# BLE_Mate2.net
KiCad netlist of a schematic drawn in EAGLE
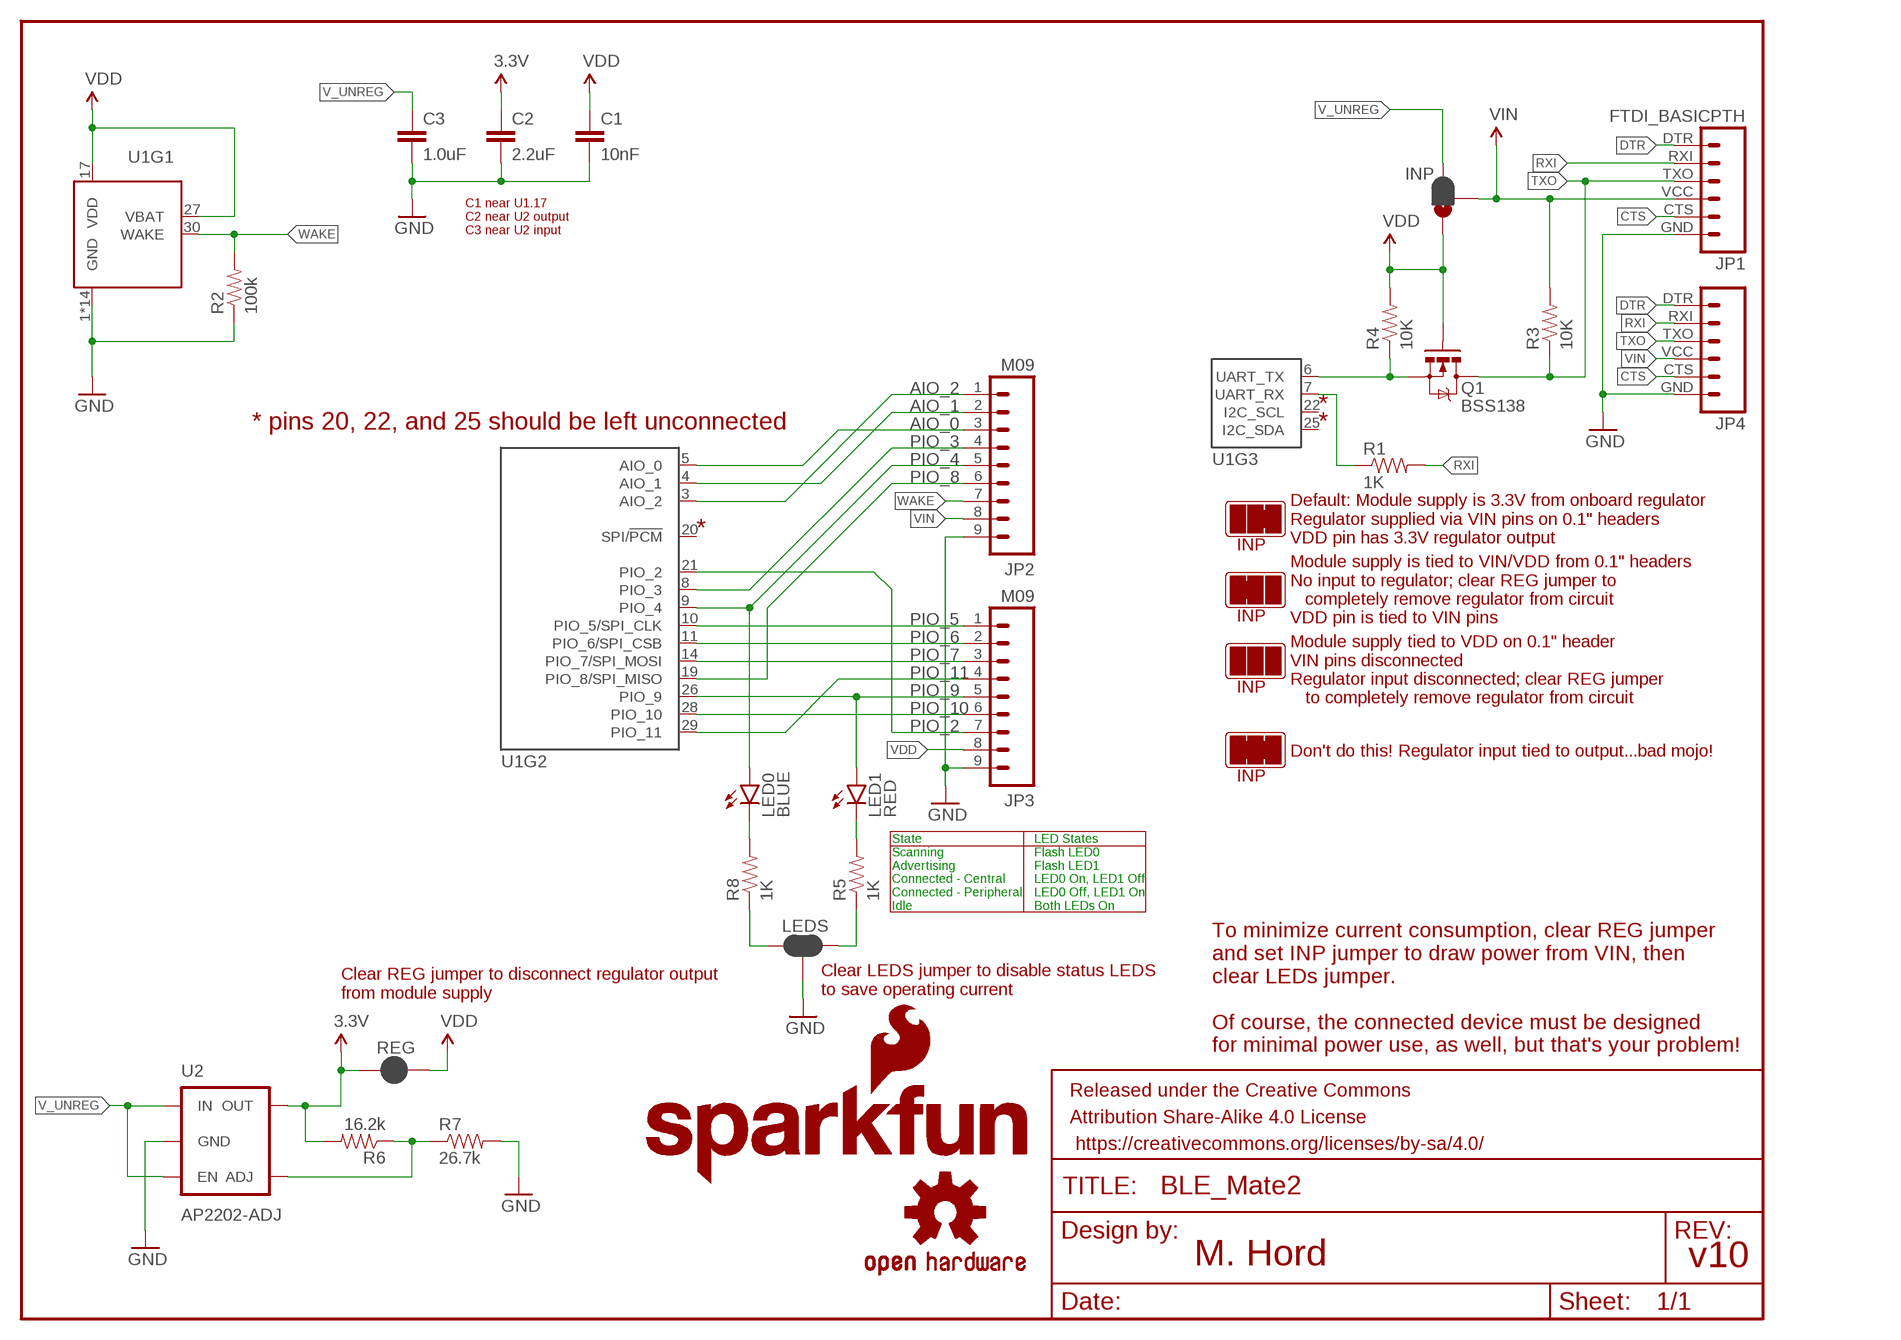
[diagram p0: schematic, sheet 1]

(export (version "E")
  (design (tool "Eeschema 10.0.6"))
  (components
    (comp (ref "C1")
      (value "10nF")
      (footprint "eagle-import:0603-CAP")
      (libsource (lib "eagle-import") (part "10NF/10000PF-50V-10%(0603)"))
    )
    (comp (ref "C2")
      (value "2.2uF")
      (footprint "eagle-import:0603-CAP")
      (libsource (lib "eagle-import") (part "2.2UF-10V-20%(0603)"))
    )
    (comp (ref "C3")
      (value "1.0uF")
      (footprint "eagle-import:0603-CAP")
      (libsource (lib "eagle-import") (part "1.0UF-16V-10%(0603)"))
    )
    (comp (ref "FRAME1")
      (value "FRAME-LETTER")
      (footprint "eagle-import:CREATIVE_COMMONS")
      (libsource (lib "eagle-import") (part "FRAME-LETTER"))
    )
    (comp (ref "INP")
      (value "JUMPER-PAD-3-2OF3_NC_BY_PASTE")
      (footprint "eagle-import:PAD-JUMPER-3-2OF3_NC_BY_PASTE_YES_SILK_FULL_BOX")
      (libsource (lib "eagle-import") (part "JUMPER-PAD-3-2OF3_NC_BY_PASTE"))
    )
    (comp (ref "JP1")
      (value "FTDI_BASICPTH")
      (footprint "eagle-import:FTDI_BASIC")
      (libsource (lib "eagle-import") (part "FTDI_BASICPTH"))
    )
    (comp (ref "JP2")
      (value "M09")
      (footprint "eagle-import:1X09")
      (libsource (lib "eagle-import") (part "M09"))
    )
    (comp (ref "JP3")
      (value "M09")
      (footprint "eagle-import:1X09")
      (libsource (lib "eagle-import") (part "M09"))
    )
    (comp (ref "JP4")
      (value "M06SIP")
      (footprint "eagle-import:1X06")
      (libsource (lib "eagle-import") (part "M06SIP"))
    )
    (comp (ref "LED0")
      (value "BLUE")
      (footprint "eagle-import:LED-0603")
      (libsource (lib "eagle-import") (part "LED-BLUE0603"))
    )
    (comp (ref "LED1")
      (value "RED")
      (footprint "eagle-import:LED-0603")
      (libsource (lib "eagle-import") (part "LED-RED0603"))
    )
    (comp (ref "LEDS")
      (value "JUMPER-PAD-3-NC_BY_PASTE")
      (footprint "eagle-import:PAD-JUMPER-3-NC_BY_PASTE_YES_SILK_FULL_BOX")
      (libsource (lib "eagle-import") (part "JUMPER-PAD-3-NC_BY_PASTE"))
    )
    (comp (ref "LOGO1")
      (value "SFE_LOGO_NAME.1_INCH")
      (footprint "eagle-import:SFE_LOGO_NAME_.1")
      (libsource (lib "eagle-import") (part "SFE_LOGO_NAME.1_INCH"))
    )
    (comp (ref "LOGO2")
      (value "OSHW-LOGOS")
      (footprint "eagle-import:OSHW-LOGO-S")
      (libsource (lib "eagle-import") (part "OSHW-LOGOS"))
    )
    (comp (ref "LOGO3")
      (value "SFE_LOGO_NAME_FLAME.1_INCH")
      (footprint "eagle-import:SFE_LOGO_NAME_FLAME_.1")
      (libsource (lib "eagle-import") (part "SFE_LOGO_NAME_FLAME.1_INCH"))
    )
    (comp (ref "LOGO4")
      (value "OSHW-LOGOS")
      (footprint "eagle-import:OSHW-LOGO-S")
      (libsource (lib "eagle-import") (part "OSHW-LOGOS"))
    )
    (comp (ref "Q1")
      (value "BSS138")
      (footprint "eagle-import:SOT23")
      (libsource (lib "eagle-import") (part "MOSFET-NCHANNELBSS138"))
    )
    (comp (ref "R1")
      (value "1K")
      (footprint "eagle-import:0603-RES")
      (libsource (lib "eagle-import") (part "1KOHM1/10W1%(0603)"))
    )
    (comp (ref "R2")
      (value "100k")
      (footprint "eagle-import:0603-RES")
      (libsource (lib "eagle-import") (part "100KOHM1/10W1%(0603)"))
    )
    (comp (ref "R3")
      (value "10K")
      (footprint "eagle-import:0603-RES")
      (libsource (lib "eagle-import") (part "10KOHM1/10W1%(0603)0603"))
    )
    (comp (ref "R4")
      (value "10K")
      (footprint "eagle-import:0603-RES")
      (libsource (lib "eagle-import") (part "10KOHM1/10W1%(0603)0603"))
    )
    (comp (ref "R5")
      (value "1K")
      (footprint "eagle-import:0603-RES")
      (libsource (lib "eagle-import") (part "1KOHM1/10W1%(0603)"))
    )
    (comp (ref "R6")
      (value "16.2k")
      (footprint "eagle-import:0603-RES")
      (libsource (lib "eagle-import") (part "16.2KOHM1/10W1%(0603)"))
    )
    (comp (ref "R7")
      (value "26.7k")
      (footprint "eagle-import:0603-RES")
      (libsource (lib "eagle-import") (part "16.2KOHM1/10W1%(0603)"))
    )
    (comp (ref "R8")
      (value "1K")
      (footprint "eagle-import:0603-RES")
      (libsource (lib "eagle-import") (part "1KOHM1/10W1%(0603)"))
    )
    (comp (ref "REG")
      (value "JUMPER-PAD-2-NC_BY_PASTE")
      (footprint "eagle-import:PAD-JUMPER-2-NC_BY_PASTE_YES_SILK")
      (libsource (lib "eagle-import") (part "JUMPER-PAD-2-NC_BY_PASTE"))
    )
    (comp (ref "U1")
      (value "BC118")
      (footprint "eagle-import:BC118")
      (libsource (lib "eagle-import") (part "BC118"))
    )
    (comp (ref "U2")
      (value "AP2202-ADJ")
      (footprint "eagle-import:SOT23-5")
      (libsource (lib "eagle-import") (part "AP2202-ADJ"))
    )
  )
  (nets
    (net (code "1") (name "/AIO_0") (class "Default")
      (node (ref "JP2") (pin "3") (pinfunction "3_3") (pintype "passive"))
      (node (ref "U1") (pin "5") (pinfunction "AIO_0_5") (pintype "bidirectional"))
    )
    (net (code "2") (name "/AIO_1") (class "Default")
      (node (ref "JP2") (pin "2") (pinfunction "2_2") (pintype "passive"))
      (node (ref "U1") (pin "4") (pinfunction "AIO_1_4") (pintype "bidirectional"))
    )
    (net (code "3") (name "/AIO_2") (class "Default")
      (node (ref "JP2") (pin "1") (pinfunction "1_1") (pintype "passive"))
      (node (ref "U1") (pin "3") (pinfunction "AIO_2_3") (pintype "bidirectional"))
    )
    (net (code "4") (name "/PIO_2") (class "Default")
      (node (ref "JP3") (pin "7") (pinfunction "7_7") (pintype "passive"))
      (node (ref "U1") (pin "21") (pinfunction "PIO_2_21") (pintype "bidirectional"))
    )
    (net (code "5") (name "/PIO_3") (class "Default")
      (node (ref "JP2") (pin "4") (pinfunction "4_4") (pintype "passive"))
      (node (ref "U1") (pin "8") (pinfunction "PIO_3_8") (pintype "bidirectional"))
    )
    (net (code "6") (name "/PIO_4") (class "Default")
      (node (ref "JP2") (pin "5") (pinfunction "5_5") (pintype "passive"))
      (node (ref "LED0") (pin "A") (pinfunction "A_A") (pintype "passive"))
      (node (ref "U1") (pin "9") (pinfunction "PIO_4_9") (pintype "bidirectional"))
    )
    (net (code "7") (name "/PIO_5") (class "Default")
      (node (ref "JP3") (pin "1") (pinfunction "1_1") (pintype "passive"))
      (node (ref "U1") (pin "10") (pinfunction "PIO_5/SPI_CLK_10") (pintype "bidirectional"))
    )
    (net (code "8") (name "/PIO_6") (class "Default")
      (node (ref "JP3") (pin "2") (pinfunction "2_2") (pintype "passive"))
      (node (ref "U1") (pin "11") (pinfunction "PIO_6/SPI_CSB_11") (pintype "bidirectional"))
    )
    (net (code "9") (name "/PIO_7") (class "Default")
      (node (ref "JP3") (pin "3") (pinfunction "3_3") (pintype "passive"))
      (node (ref "U1") (pin "14") (pinfunction "PIO_7/SPI_MOSI_14") (pintype "bidirectional"))
    )
    (net (code "10") (name "/PIO_8") (class "Default")
      (node (ref "JP2") (pin "6") (pinfunction "6_6") (pintype "passive"))
      (node (ref "U1") (pin "19") (pinfunction "PIO_8/SPI_MISO_19") (pintype "bidirectional"))
    )
    (net (code "11") (name "/PIO_9") (class "Default")
      (node (ref "JP3") (pin "5") (pinfunction "5_5") (pintype "passive"))
      (node (ref "LED1") (pin "A") (pinfunction "A_A") (pintype "passive"))
      (node (ref "U1") (pin "26") (pinfunction "PIO_9_26") (pintype "bidirectional"))
    )
    (net (code "12") (name "/PIO_10") (class "Default")
      (node (ref "JP3") (pin "6") (pinfunction "6_6") (pintype "passive"))
      (node (ref "U1") (pin "28") (pinfunction "PIO_10_28") (pintype "bidirectional"))
    )
    (net (code "13") (name "/PIO_11") (class "Default")
      (node (ref "JP3") (pin "4") (pinfunction "4_4") (pintype "passive"))
      (node (ref "U1") (pin "29") (pinfunction "PIO_11_29") (pintype "bidirectional"))
    )
    (net (code "14") (name "3.3V") (class "Default")
      (node (ref "C2") (pin "1") (pinfunction "1_1") (pintype "passive"))
      (node (ref "R6") (pin "2") (pinfunction "2_2") (pintype "passive"))
      (node (ref "REG") (pin "1") (pinfunction "1_1") (pintype "passive"))
      (node (ref "U2") (pin "5") (pinfunction "OUT_5") (pintype "passive"))
    )
    (net (code "15") (name "CTS") (class "Default")
      (node (ref "JP1") (pin "CTS") (pinfunction "5_CTS") (pintype "passive"))
      (node (ref "JP4") (pin "CTS") (pinfunction "5_CTS") (pintype "passive"))
    )
    (net (code "16") (name "DTR") (class "Default")
      (node (ref "JP1") (pin "DTR") (pinfunction "1_DTR") (pintype "passive"))
      (node (ref "JP4") (pin "DTR") (pinfunction "1_DTR") (pintype "passive"))
    )
    (net (code "17") (name "GND") (class "Default")
      (node (ref "C1") (pin "2") (pinfunction "2_2") (pintype "passive"))
      (node (ref "C2") (pin "2") (pinfunction "2_2") (pintype "passive"))
      (node (ref "C3") (pin "2") (pinfunction "2_2") (pintype "passive"))
      (node (ref "JP1") (pin "GND") (pinfunction "6_GND") (pintype "passive"))
      (node (ref "JP2") (pin "9") (pinfunction "9_9") (pintype "passive"))
      (node (ref "JP3") (pin "9") (pinfunction "9_9") (pintype "passive"))
      (node (ref "JP4") (pin "GND") (pinfunction "6_GND") (pintype "passive"))
      (node (ref "LEDS") (pin "2") (pinfunction "2_2") (pintype "passive"))
      (node (ref "R2") (pin "1") (pinfunction "1_1") (pintype "passive"))
      (node (ref "R7") (pin "2") (pinfunction "2_2") (pintype "passive"))
      (node (ref "U1") (pin "1") (pinfunction "GND_1") (pintype "bidirectional"))
      (node (ref "U1") (pin "12") (pinfunction "GND_12") (pintype "bidirectional"))
      (node (ref "U1") (pin "13") (pinfunction "GND_13") (pintype "bidirectional"))
      (node (ref "U1") (pin "15") (pinfunction "GND_15") (pintype "bidirectional"))
      (node (ref "U1") (pin "16") (pinfunction "GND_16") (pintype "bidirectional"))
      (node (ref "U1") (pin "18") (pinfunction "GND_18") (pintype "bidirectional"))
      (node (ref "U1") (pin "2") (pinfunction "GND_2") (pintype "bidirectional"))
      (node (ref "U1") (pin "23") (pinfunction "GND_23") (pintype "bidirectional"))
      (node (ref "U1") (pin "24") (pinfunction "GND_24") (pintype "bidirectional"))
      (node (ref "U1") (pin "31") (pinfunction "GND_31") (pintype "bidirectional"))
      (node (ref "U1") (pin "32") (pinfunction "GND_32") (pintype "bidirectional"))
      (node (ref "U1") (pin "33") (pinfunction "GND_33") (pintype "bidirectional"))
      (node (ref "U1") (pin "34") (pinfunction "GND_34") (pintype "bidirectional"))
      (node (ref "U1") (pin "35") (pinfunction "GND_35") (pintype "bidirectional"))
      (node (ref "U2") (pin "2") (pinfunction "GND_2") (pintype "input"))
    )
    (net (code "18") (name "Net-(LED0-PadC)") (class "Default")
      (node (ref "LED0") (pin "C") (pinfunction "C_C") (pintype "passive"))
      (node (ref "R8") (pin "2") (pinfunction "2_2") (pintype "passive"))
    )
    (net (code "19") (name "Net-(LED1-PadC)") (class "Default")
      (node (ref "LED1") (pin "C") (pinfunction "C_C") (pintype "passive"))
      (node (ref "R5") (pin "2") (pinfunction "2_2") (pintype "passive"))
    )
    (net (code "20") (name "Net-(LEDS-Pad1)") (class "Default")
      (node (ref "LEDS") (pin "1") (pinfunction "1_1") (pintype "passive"))
      (node (ref "R8") (pin "1") (pinfunction "1_1") (pintype "passive"))
    )
    (net (code "21") (name "Net-(LEDS-Pad3)") (class "Default")
      (node (ref "LEDS") (pin "3") (pinfunction "3_3") (pintype "passive"))
      (node (ref "R5") (pin "1") (pinfunction "1_1") (pintype "passive"))
    )
    (net (code "22") (name "Net-(Q1-S)") (class "Default")
      (node (ref "Q1") (pin "2") (pinfunction "S_2") (pintype "passive"))
      (node (ref "R4") (pin "1") (pinfunction "1_1") (pintype "passive"))
      (node (ref "U1") (pin "6") (pinfunction "UART_TX_6") (pintype "bidirectional"))
    )
    (net (code "23") (name "Net-(U1C-UART_RX)") (class "Default")
      (node (ref "R1") (pin "1") (pinfunction "1_1") (pintype "passive"))
      (node (ref "U1") (pin "7") (pinfunction "UART_RX_7") (pintype "bidirectional"))
    )
    (net (code "24") (name "Net-(U2-ADJ)") (class "Default")
      (node (ref "R6") (pin "1") (pinfunction "1_1") (pintype "passive"))
      (node (ref "R7") (pin "1") (pinfunction "1_1") (pintype "passive"))
      (node (ref "U2") (pin "4") (pinfunction "ADJ_4") (pintype "input"))
    )
    (net (code "25") (name "RXI") (class "Default")
      (node (ref "JP1") (pin "RXI") (pinfunction "2_RXI") (pintype "passive"))
      (node (ref "JP4") (pin "RXI") (pinfunction "2_RXI") (pintype "passive"))
      (node (ref "R1") (pin "2") (pinfunction "2_2") (pintype "passive"))
    )
    (net (code "26") (name "TXO") (class "Default")
      (node (ref "JP1") (pin "TXO") (pinfunction "3_TXO") (pintype "passive"))
      (node (ref "JP4") (pin "TXO") (pinfunction "3_TXO") (pintype "passive"))
      (node (ref "Q1") (pin "3") (pinfunction "D_3") (pintype "passive"))
      (node (ref "R3") (pin "1") (pinfunction "1_1") (pintype "passive"))
    )
    (net (code "27") (name "VDD") (class "Default")
      (node (ref "C1") (pin "1") (pinfunction "1_1") (pintype "passive"))
      (node (ref "INP") (pin "1") (pinfunction "1_1") (pintype "passive"))
      (node (ref "JP3") (pin "8") (pinfunction "8_8") (pintype "passive"))
      (node (ref "Q1") (pin "1") (pinfunction "G_1") (pintype "passive"))
      (node (ref "R4") (pin "2") (pinfunction "2_2") (pintype "passive"))
      (node (ref "REG") (pin "2") (pinfunction "2_2") (pintype "passive"))
      (node (ref "U1") (pin "17") (pinfunction "VDD_17") (pintype "bidirectional"))
      (node (ref "U1") (pin "27") (pinfunction "VBAT_27") (pintype "bidirectional"))
    )
    (net (code "28") (name "VIN") (class "Default")
      (node (ref "INP") (pin "2") (pinfunction "2_2") (pintype "passive"))
      (node (ref "JP1") (pin "VCC") (pinfunction "4_VCC") (pintype "passive"))
      (node (ref "JP2") (pin "8") (pinfunction "8_8") (pintype "passive"))
      (node (ref "JP4") (pin "VCC") (pinfunction "4_VCC") (pintype "passive"))
      (node (ref "R3") (pin "2") (pinfunction "2_2") (pintype "passive"))
    )
    (net (code "29") (name "V_UNREG") (class "Default")
      (node (ref "C3") (pin "1") (pinfunction "1_1") (pintype "passive"))
      (node (ref "INP") (pin "3") (pinfunction "3_3") (pintype "passive"))
      (node (ref "U2") (pin "1") (pinfunction "IN_1") (pintype "input"))
      (node (ref "U2") (pin "3") (pinfunction "EN_3") (pintype "input"))
    )
    (net (code "30") (name "WAKE") (class "Default")
      (node (ref "JP2") (pin "7") (pinfunction "7_7") (pintype "passive"))
      (node (ref "R2") (pin "2") (pinfunction "2_2") (pintype "passive"))
      (node (ref "U1") (pin "30") (pinfunction "WAKE_30") (pintype "bidirectional"))
    )
    (net (code "31") (name "unconnected-(U1B-SPI{slash}~{PCM}-Pad20)") (class "Default")
      (node (ref "U1") (pin "20") (pinfunction "SPI/~{PCM}_20") (pintype "bidirectional"))
    )
    (net (code "32") (name "unconnected-(U1C-I2C_SCL-Pad22)") (class "Default")
      (node (ref "U1") (pin "22") (pinfunction "I2C_SCL_22") (pintype "bidirectional"))
    )
    (net (code "33") (name "unconnected-(U1C-I2C_SDA-Pad25)") (class "Default")
      (node (ref "U1") (pin "25") (pinfunction "I2C_SDA_25") (pintype "bidirectional"))
    )
  )
)
